# fuelboxmp3.net
KiCad netlist of a schematic drawn in EAGLE
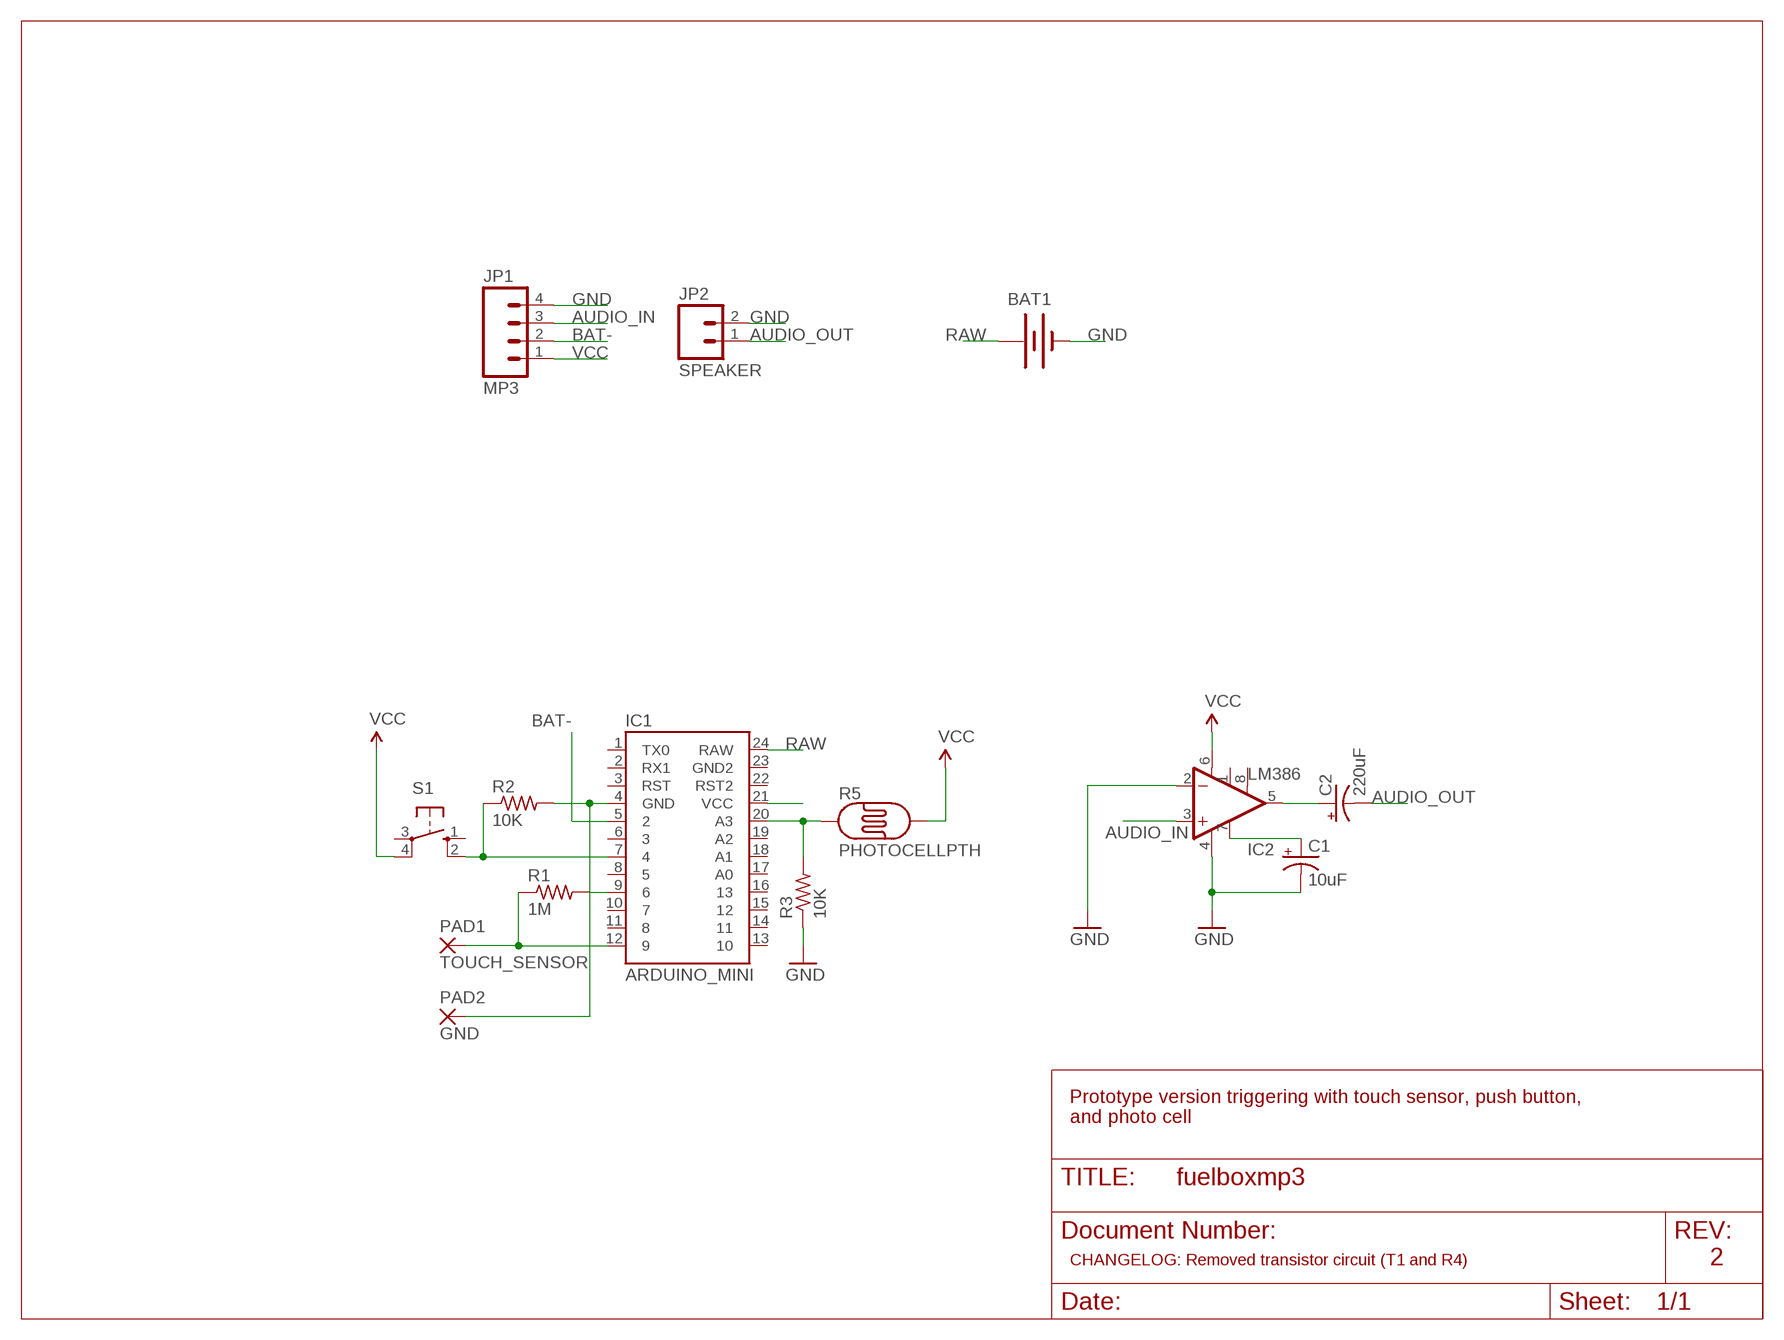
[diagram p0: schematic, sheet 1]

(export (version "E")
  (design (tool "Eeschema 10.0.6"))
  (components
    (comp (ref "BAT1")
      (value "BATTERY1100")
      (footprint "eagle-import:LIPO-1100MAH")
      (libsource (lib "eagle-import") (part "BATTERY1100"))
    )
    (comp (ref "C1")
      (value "10uF")
      (footprint "eagle-import:E2,5-5")
      (libsource (lib "eagle-import") (part "CPOL-USE2.5-5"))
    )
    (comp (ref "C2")
      (value "220uF")
      (footprint "eagle-import:E2,5-6")
      (libsource (lib "eagle-import") (part "CPOL-USE2.5-6"))
    )
    (comp (ref "IC1")
      (value "ARDUINO_MINI")
      (footprint "eagle-import:ARDUINO_MINI")
      (libsource (lib "eagle-import") (part "ARDUINO_MINI"))
    )
    (comp (ref "IC2")
      (value "LM386")
      (footprint "eagle-import:DIP08")
      (libsource (lib "eagle-import") (part "LM386"))
    )
    (comp (ref "JP1")
      (value "MP3")
      (footprint "eagle-import:1X04")
      (libsource (lib "eagle-import") (part "M04PTH"))
    )
    (comp (ref "JP2")
      (value "SPEAKER")
      (footprint "eagle-import:1X02")
      (libsource (lib "eagle-import") (part "M02PTH"))
    )
    (comp (ref "PAD1")
      (value "TOUCH_SENSOR")
      (footprint "eagle-import:3,81_1,1")
      (libsource (lib "eagle-import") (part "WIREPAD3,81/1,1"))
    )
    (comp (ref "PAD2")
      (value "GND")
      (footprint "eagle-import:3,81_1,1")
      (libsource (lib "eagle-import") (part "WIREPAD3,81/1,1"))
    )
    (comp (ref "R1")
      (value "1M")
      (footprint "eagle-import:0204_7")
      (libsource (lib "eagle-import") (part "R-US_0204/7"))
    )
    (comp (ref "R2")
      (value "10K")
      (footprint "eagle-import:0204_7")
      (libsource (lib "eagle-import") (part "R-US_0204/7"))
    )
    (comp (ref "R3")
      (value "10K")
      (footprint "eagle-import:0204_7")
      (libsource (lib "eagle-import") (part "R-US_0204/7"))
    )
    (comp (ref "R5")
      (value "PHOTOCELLPTH")
      (footprint "eagle-import:PHOTOCELL")
      (libsource (lib "eagle-import") (part "PHOTOCELLPTH"))
    )
    (comp (ref "S1")
      (value "10-XX")
      (footprint "eagle-import:B3F-10XX")
      (fields (field (name "MPN") "B3F-1000"))
      (libsource (lib "eagle-import") (part "10-XX"))
    )
  )
  (nets
    (net (code "1") (name "/AUDIO_IN") (class "Default")
      (node (ref "IC2") (pin "3") (pinfunction "+IN_3") (pintype "input"))
      (node (ref "JP1") (pin "3") (pinfunction "3_3") (pintype "passive"))
    )
    (net (code "2") (name "/AUDIO_OUT") (class "Default")
      (node (ref "C2") (pin "-") (pinfunction "-_-") (pintype "passive"))
      (node (ref "JP2") (pin "1") (pinfunction "1_1") (pintype "passive"))
    )
    (net (code "3") (name "/BAT-") (class "Default")
      (node (ref "IC1") (pin "5") (pinfunction "2_5") (pintype "bidirectional"))
      (node (ref "JP1") (pin "2") (pinfunction "2_2") (pintype "passive"))
    )
    (net (code "4") (name "/RAW") (class "Default")
      (node (ref "BAT1") (pin "+") (pinfunction "+_+") (pintype "power_in"))
      (node (ref "IC1") (pin "24") (pinfunction "RAW_24") (pintype "bidirectional"))
    )
    (net (code "5") (name "GND") (class "Default")
      (node (ref "BAT1") (pin "-") (pinfunction "-_-") (pintype "power_in"))
      (node (ref "C1") (pin "-") (pinfunction "-_-") (pintype "passive"))
      (node (ref "IC1") (pin "4") (pinfunction "GND_4") (pintype "bidirectional"))
      (node (ref "IC2") (pin "2") (pinfunction "-IN_2") (pintype "input"))
      (node (ref "IC2") (pin "4") (pinfunction "V-_4") (pintype "power_in"))
      (node (ref "JP1") (pin "4") (pinfunction "4_4") (pintype "passive"))
      (node (ref "JP2") (pin "2") (pinfunction "2_2") (pintype "passive"))
      (node (ref "PAD2") (pin "1") (pinfunction "P_1") (pintype "passive"))
      (node (ref "R2") (pin "2") (pinfunction "2_2") (pintype "passive"))
      (node (ref "R3") (pin "1") (pinfunction "1_1") (pintype "passive"))
    )
    (net (code "6") (name "Net-(IC1-4)") (class "Default")
      (node (ref "IC1") (pin "7") (pinfunction "4_7") (pintype "bidirectional"))
      (node (ref "R2") (pin "1") (pinfunction "1_1") (pintype "passive"))
      (node (ref "S1") (pin "2") (pinfunction "S1_2") (pintype "passive"))
    )
    (net (code "7") (name "Net-(IC1-6)") (class "Default")
      (node (ref "IC1") (pin "9") (pinfunction "6_9") (pintype "bidirectional"))
      (node (ref "R1") (pin "2") (pinfunction "2_2") (pintype "passive"))
    )
    (net (code "8") (name "Net-(IC1-9)") (class "Default")
      (node (ref "IC1") (pin "12") (pinfunction "9_12") (pintype "bidirectional"))
      (node (ref "PAD1") (pin "1") (pinfunction "P_1") (pintype "passive"))
      (node (ref "R1") (pin "1") (pinfunction "1_1") (pintype "passive"))
    )
    (net (code "9") (name "Net-(IC1-A3)") (class "Default")
      (node (ref "IC1") (pin "20") (pinfunction "A3_20") (pintype "bidirectional"))
      (node (ref "R3") (pin "2") (pinfunction "2_2") (pintype "passive"))
      (node (ref "R5") (pin "1") (pinfunction "P$1_1") (pintype "bidirectional"))
    )
    (net (code "10") (name "Net-(IC2-BP)") (class "Default")
      (node (ref "C1") (pin "+") (pinfunction "+_+") (pintype "passive"))
      (node (ref "IC2") (pin "7") (pinfunction "BP_7") (pintype "bidirectional"))
    )
    (net (code "11") (name "Net-(IC2-OUT)") (class "Default")
      (node (ref "C2") (pin "+") (pinfunction "+_+") (pintype "passive"))
      (node (ref "IC2") (pin "5") (pinfunction "OUT_5") (pintype "output"))
    )
    (net (code "12") (name "VCC") (class "Default")
      (node (ref "IC1") (pin "21") (pinfunction "VCC_21") (pintype "bidirectional"))
      (node (ref "IC2") (pin "6") (pinfunction "V+_6") (pintype "power_in"))
      (node (ref "JP1") (pin "1") (pinfunction "1_1") (pintype "passive"))
      (node (ref "R5") (pin "2") (pinfunction "P$2_2") (pintype "bidirectional"))
      (node (ref "S1") (pin "4") (pinfunction "P1_4") (pintype "passive"))
    )
    (net (code "13") (name "unconnected-(IC1-3-Pad6)") (class "Default")
      (node (ref "IC1") (pin "6") (pinfunction "3_6") (pintype "bidirectional"))
    )
    (net (code "14") (name "unconnected-(IC1-5-Pad8)") (class "Default")
      (node (ref "IC1") (pin "8") (pinfunction "5_8") (pintype "bidirectional"))
    )
    (net (code "15") (name "unconnected-(IC1-7-Pad10)") (class "Default")
      (node (ref "IC1") (pin "10") (pinfunction "7_10") (pintype "bidirectional"))
    )
    (net (code "16") (name "unconnected-(IC1-8-Pad11)") (class "Default")
      (node (ref "IC1") (pin "11") (pinfunction "8_11") (pintype "bidirectional"))
    )
    (net (code "17") (name "unconnected-(IC1-10-Pad13)") (class "Default")
      (node (ref "IC1") (pin "13") (pinfunction "10_13") (pintype "bidirectional"))
    )
    (net (code "18") (name "unconnected-(IC1-11-Pad14)") (class "Default")
      (node (ref "IC1") (pin "14") (pinfunction "11_14") (pintype "bidirectional"))
    )
    (net (code "19") (name "unconnected-(IC1-12-Pad15)") (class "Default")
      (node (ref "IC1") (pin "15") (pinfunction "12_15") (pintype "bidirectional"))
    )
    (net (code "20") (name "unconnected-(IC1-13-Pad16)") (class "Default")
      (node (ref "IC1") (pin "16") (pinfunction "13_16") (pintype "bidirectional"))
    )
    (net (code "21") (name "unconnected-(IC1-A0-Pad17)") (class "Default")
      (node (ref "IC1") (pin "17") (pinfunction "A0_17") (pintype "bidirectional"))
    )
    (net (code "22") (name "unconnected-(IC1-A1-Pad18)") (class "Default")
      (node (ref "IC1") (pin "18") (pinfunction "A1_18") (pintype "bidirectional"))
    )
    (net (code "23") (name "unconnected-(IC1-A2-Pad19)") (class "Default")
      (node (ref "IC1") (pin "19") (pinfunction "A2_19") (pintype "bidirectional"))
    )
    (net (code "24") (name "unconnected-(IC1-GND2-Pad23)") (class "Default")
      (node (ref "IC1") (pin "23") (pinfunction "GND2_23") (pintype "bidirectional"))
    )
    (net (code "25") (name "unconnected-(IC1-RST-Pad3)") (class "Default")
      (node (ref "IC1") (pin "3") (pinfunction "RST_3") (pintype "bidirectional"))
    )
    (net (code "26") (name "unconnected-(IC1-RST2-Pad22)") (class "Default")
      (node (ref "IC1") (pin "22") (pinfunction "RST2_22") (pintype "bidirectional"))
    )
    (net (code "27") (name "unconnected-(IC1-RX1-Pad2)") (class "Default")
      (node (ref "IC1") (pin "2") (pinfunction "RX1_2") (pintype "bidirectional"))
    )
    (net (code "28") (name "unconnected-(IC1-TX0-Pad1)") (class "Default")
      (node (ref "IC1") (pin "1") (pinfunction "TX0_1") (pintype "bidirectional"))
    )
    (net (code "29") (name "unconnected-(IC2-GAIN-Pad1)") (class "Default")
      (node (ref "IC2") (pin "1") (pinfunction "GAIN_1") (pintype "bidirectional"))
    )
    (net (code "30") (name "unconnected-(IC2-GAIN-Pad8)") (class "Default")
      (node (ref "IC2") (pin "8") (pinfunction "GAIN_8") (pintype "bidirectional"))
    )
    (net (code "31") (name "unconnected-(S1-P-Pad3)") (class "Default")
      (node (ref "S1") (pin "3") (pinfunction "P_3") (pintype "passive"))
    )
    (net (code "32") (name "unconnected-(S1-S-Pad1)") (class "Default")
      (node (ref "S1") (pin "1") (pinfunction "S_1") (pintype "passive"))
    )
  )
)
